# LitKit.net
KiCad netlist of a schematic drawn in EAGLE
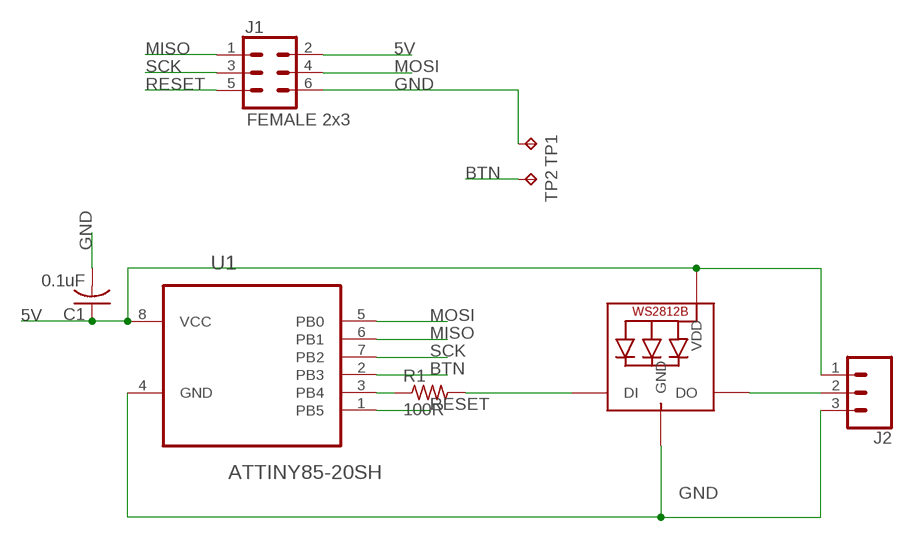
[diagram p0: schematic, sheet 1]

(export (version "E")
  (design (tool "Eeschema 10.0.6"))
  (components
    (comp (ref "C1")
      (value "0.1uF")
      (footprint "eagle-import:C0805")
      (libsource (lib "eagle-import") (part "C-USC0805"))
    )
    (comp (ref "J1")
      (value "FEMALE 2x3")
      (footprint "eagle-import:2X3")
      (libsource (lib "eagle-import") (part "CONN_03X2FEMALE"))
    )
    (comp (ref "J2")
      (value "CONN_031X03_NO_SILK")
      (footprint "eagle-import:1X03_NO_SILK")
      (libsource (lib "eagle-import") (part "CONN_031X03_NO_SILK"))
    )
    (comp (ref "LED1")
      (value "WS2812B3535")
      (footprint "eagle-import:LED3535")
      (libsource (lib "eagle-import") (part "WS2812B3535"))
    )
    (comp (ref "R1")
      (value "100R")
      (footprint "eagle-import:R0805")
      (libsource (lib "eagle-import") (part "R-US_R0805"))
    )
    (comp (ref "TP1")
      (value "TPB1,27")
      (footprint "eagle-import:B1,27")
      (libsource (lib "eagle-import") (part "TPB1,27"))
    )
    (comp (ref "TP2")
      (value "TPB1,27")
      (footprint "eagle-import:B1,27")
      (libsource (lib "eagle-import") (part "TPB1,27"))
    )
    (comp (ref "U1")
      (value "ATTINY85-20SH")
      (footprint "eagle-import:SOIC127P798X216-8N")
      (fields (field (name "MF") "Microchip"))
      (libsource (lib "eagle-import") (part "ATTINY85-20SH"))
    )
  )
  (nets
    (net (code "1") (name "/5V") (class "Default")
      (node (ref "C1") (pin "1") (pinfunction "1_1") (pintype "passive"))
      (node (ref "J1") (pin "2") (pinfunction "2_2") (pintype "bidirectional"))
      (node (ref "J2") (pin "1") (pinfunction "1_1") (pintype "passive"))
      (node (ref "LED1") (pin "2") (pinfunction "VDD_2") (pintype "power_in"))
      (node (ref "U1") (pin "8") (pinfunction "VCC_8") (pintype "power_in"))
    )
    (net (code "2") (name "/BTN") (class "Default")
      (node (ref "TP2") (pin "TP") (pinfunction "TP_TP") (pintype "input"))
      (node (ref "U1") (pin "2") (pinfunction "PB3_2") (pintype "bidirectional"))
    )
    (net (code "3") (name "/GND") (class "Default")
      (node (ref "C1") (pin "2") (pinfunction "2_2") (pintype "passive"))
      (node (ref "J1") (pin "6") (pinfunction "6_6") (pintype "bidirectional"))
      (node (ref "J2") (pin "3") (pinfunction "3_3") (pintype "passive"))
      (node (ref "LED1") (pin "4") (pinfunction "GND_4") (pintype "power_in"))
      (node (ref "TP1") (pin "TP") (pinfunction "TP_TP") (pintype "input"))
      (node (ref "U1") (pin "4") (pinfunction "GND_4") (pintype "passive"))
    )
    (net (code "4") (name "/MISO") (class "Default")
      (node (ref "J1") (pin "1") (pinfunction "1_1") (pintype "bidirectional"))
      (node (ref "U1") (pin "6") (pinfunction "PB1_6") (pintype "bidirectional"))
    )
    (net (code "5") (name "/MOSI") (class "Default")
      (node (ref "J1") (pin "4") (pinfunction "4_4") (pintype "bidirectional"))
      (node (ref "U1") (pin "5") (pinfunction "PB0_5") (pintype "bidirectional"))
    )
    (net (code "6") (name "/RESET") (class "Default")
      (node (ref "J1") (pin "5") (pinfunction "5_5") (pintype "bidirectional"))
      (node (ref "U1") (pin "1") (pinfunction "PB5_1") (pintype "bidirectional"))
    )
    (net (code "7") (name "/SCK") (class "Default")
      (node (ref "J1") (pin "3") (pinfunction "3_3") (pintype "bidirectional"))
      (node (ref "U1") (pin "7") (pinfunction "PB2_7") (pintype "bidirectional"))
    )
    (net (code "8") (name "Net-(LED1-DI)") (class "Default")
      (node (ref "LED1") (pin "1") (pinfunction "DI_1") (pintype "input"))
      (node (ref "R1") (pin "2") (pinfunction "2_2") (pintype "passive"))
    )
    (net (code "9") (name "Net-(LED1-DO)") (class "Default")
      (node (ref "J2") (pin "2") (pinfunction "2_2") (pintype "passive"))
      (node (ref "LED1") (pin "3") (pinfunction "DO_3") (pintype "output"))
    )
    (net (code "10") (name "Net-(U1-PB4)") (class "Default")
      (node (ref "R1") (pin "1") (pinfunction "1_1") (pintype "passive"))
      (node (ref "U1") (pin "3") (pinfunction "PB4_3") (pintype "bidirectional"))
    )
  )
)
